# Communication.net
KiCad netlist of a schematic drawn in Altium Designer
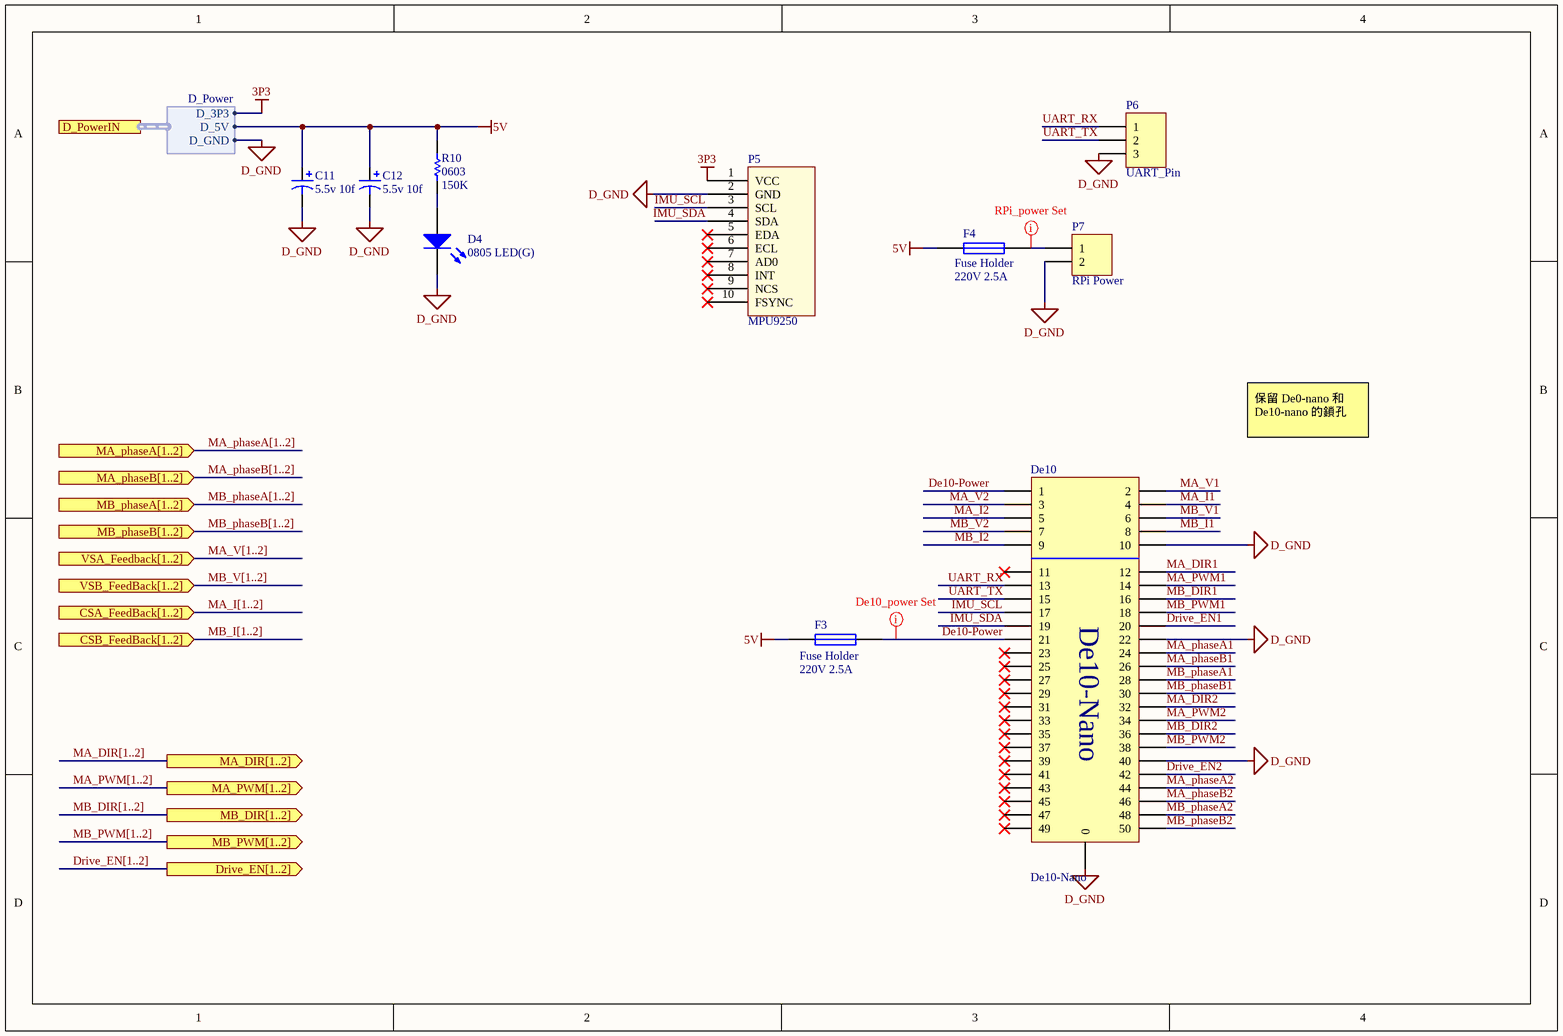
[diagram p0: Communication.SchDoc]

(export (version "E")
  (design (tool "Eeschema 10.0.6"))
  (components
    (comp (ref "C11")
      (value "5.5v 10f")
      (footprint "OWMR:SUPPYCAP-DIP_L33.0_W16.5")
      (description "Super Capacitor")
      (fields (field (name "PUBLISHER") "Altium Limited"))
      (libsource (lib "Miscellaneous Devices") (part "Cap Pol1"))
    )
    (comp (ref "C12")
      (value "5.5v 10f")
      (footprint "OWMR:SUPPYCAP-DIP_L33.0_W16.5")
      (description "Super Capacitor")
      (fields (field (name "PUBLISHER") "Altium Limited"))
      (libsource (lib "Miscellaneous Devices") (part "Cap Pol1"))
    )
    (comp (ref "D4")
      (value "0805 LED(G)")
      (footprint "OWMR:0805 SMD DIode")
      (description "Typical INFRARED GaAs LED")
      (fields (field (name "PUBLISHER") "Altium Limited"))
      (libsource (lib "Miscellaneous Devices") (part "LED0"))
    )
    (comp (ref "De10")
      (value "De10-Nano")
      (footprint "OWMR:De10-Nano")
      (libsource (lib "OWMR") (part "De10-Nano"))
    )
    (comp (ref "F3")
      (value "Fuse Holder")
      (footprint "OWMR:SMD Fuses Holder")
      (description "0451005.MRL")
      (fields (field (name "ALTIUM_VALUE") "220V 2.5A") (field (name "PUBLISHER") "Altium Limited"))
      (libsource (lib "Miscellaneous Devices") (part "Fuse 1"))
    )
    (comp (ref "F4")
      (value "Fuse Holder")
      (footprint "OWMR:SMD Fuses Holder")
      (description "0451005.MRL")
      (fields (field (name "ALTIUM_VALUE") "220V 2.5A") (field (name "PUBLISHER") "Altium Limited"))
      (libsource (lib "Miscellaneous Devices") (part "Fuse 1"))
    )
    (comp (ref "P5")
      (value "MPU9250")
      (footprint "MPU9250")
      (description "3 axis Gyro, Acceleration, Magmetic")
      (libsource (lib "OWMR") (part "IMU Pin"))
    )
    (comp (ref "P6")
      (value "UART_Pin")
      (footprint "OWMR:B3B-XH-A")
      (description "B3B-XH-A")
      (fields (field (name "PUBLISHER") "Altium Limited"))
      (libsource (lib "Miscellaneous Connectors") (part "Header 3"))
    )
    (comp (ref "P7")
      (value "RPi Power")
      (footprint "OWMR:B2B-XH-A")
      (description "B2B-XH-A")
      (fields (field (name "PUBLISHER") "Altium Limited"))
      (libsource (lib "Miscellaneous Connectors") (part "Header 2"))
    )
    (comp (ref "R10")
      (value "0603")
      (footprint "OWMR:0603 SMD Res")
      (description "Resistor")
      (fields (field (name "ALTIUM_VALUE") "150K") (field (name "PUBLISHER") "Altium Limited"))
      (libsource (lib "Miscellaneous Devices") (part "Res1"))
    )
  )
  (nets
    (net (code "2") (name "/De10-Power") (class "Default")
      (node (ref "De10") (pin "1") (pinfunction "1_1") (pintype "passive"))
      (node (ref "De10") (pin "21") (pinfunction "21_21") (pintype "passive"))
      (node (ref "F3") (pin "2") (pinfunction "2_2") (pintype "passive"))
    )
    (net (code "3") (name "/Drive_EN1") (class "Default")
      (node (ref "De10") (pin "20") (pinfunction "20_20") (pintype "passive"))
    )
    (net (code "4") (name "/Drive_EN2") (class "Default")
      (node (ref "De10") (pin "42") (pinfunction "42_42") (pintype "passive"))
    )
    (net (code "6") (name "/IMU_SCL") (class "Default")
      (node (ref "De10") (pin "17") (pinfunction "17_17") (pintype "passive"))
      (node (ref "P5") (pin "3") (pinfunction "SCL_3") (pintype "passive"))
    )
    (net (code "7") (name "/IMU_SDA") (class "Default")
      (node (ref "De10") (pin "19") (pinfunction "19_19") (pintype "passive"))
      (node (ref "P5") (pin "4") (pinfunction "SDA_4") (pintype "passive"))
    )
    (net (code "8") (name "/MA_DIR1") (class "Default")
      (node (ref "De10") (pin "12") (pinfunction "12_12") (pintype "passive"))
    )
    (net (code "9") (name "/MA_DIR2") (class "Default")
      (node (ref "De10") (pin "32") (pinfunction "32_32") (pintype "passive"))
    )
    (net (code "11") (name "/MA_I1") (class "Default")
      (node (ref "De10") (pin "4") (pinfunction "4_4") (pintype "passive"))
    )
    (net (code "12") (name "/MA_I2") (class "Default")
      (node (ref "De10") (pin "5") (pinfunction "5_5") (pintype "passive"))
    )
    (net (code "14") (name "/MA_PWM1") (class "Default")
      (node (ref "De10") (pin "14") (pinfunction "14_14") (pintype "passive"))
    )
    (net (code "15") (name "/MA_PWM2") (class "Default")
      (node (ref "De10") (pin "34") (pinfunction "34_34") (pintype "passive"))
    )
    (net (code "17") (name "/MA_V1") (class "Default")
      (node (ref "De10") (pin "2") (pinfunction "2_2") (pintype "passive"))
    )
    (net (code "18") (name "/MA_V2") (class "Default")
      (node (ref "De10") (pin "3") (pinfunction "3_3") (pintype "passive"))
    )
    (net (code "20") (name "/MA_phaseA1") (class "Default")
      (node (ref "De10") (pin "24") (pinfunction "24_24") (pintype "passive"))
    )
    (net (code "21") (name "/MA_phaseA2") (class "Default")
      (node (ref "De10") (pin "44") (pinfunction "44_44") (pintype "passive"))
    )
    (net (code "23") (name "/MA_phaseB1") (class "Default")
      (node (ref "De10") (pin "26") (pinfunction "26_26") (pintype "passive"))
    )
    (net (code "24") (name "/MA_phaseB2") (class "Default")
      (node (ref "De10") (pin "46") (pinfunction "46_46") (pintype "passive"))
    )
    (net (code "26") (name "/MB_DIR1") (class "Default")
      (node (ref "De10") (pin "16") (pinfunction "16_16") (pintype "passive"))
    )
    (net (code "27") (name "/MB_DIR2") (class "Default")
      (node (ref "De10") (pin "36") (pinfunction "36_36") (pintype "passive"))
    )
    (net (code "29") (name "/MB_I1") (class "Default")
      (node (ref "De10") (pin "8") (pinfunction "8_8") (pintype "passive"))
    )
    (net (code "30") (name "/MB_I2") (class "Default")
      (node (ref "De10") (pin "9") (pinfunction "9_9") (pintype "passive"))
    )
    (net (code "32") (name "/MB_PWM1") (class "Default")
      (node (ref "De10") (pin "18") (pinfunction "18_18") (pintype "passive"))
    )
    (net (code "33") (name "/MB_PWM2") (class "Default")
      (node (ref "De10") (pin "38") (pinfunction "38_38") (pintype "passive"))
    )
    (net (code "35") (name "/MB_V1") (class "Default")
      (node (ref "De10") (pin "6") (pinfunction "6_6") (pintype "passive"))
    )
    (net (code "36") (name "/MB_V2") (class "Default")
      (node (ref "De10") (pin "7") (pinfunction "7_7") (pintype "passive"))
    )
    (net (code "38") (name "/MB_phaseA1") (class "Default")
      (node (ref "De10") (pin "28") (pinfunction "28_28") (pintype "passive"))
    )
    (net (code "39") (name "/MB_phaseA2") (class "Default")
      (node (ref "De10") (pin "48") (pinfunction "48_48") (pintype "passive"))
    )
    (net (code "41") (name "/MB_phaseB1") (class "Default")
      (node (ref "De10") (pin "30") (pinfunction "30_30") (pintype "passive"))
    )
    (net (code "42") (name "/MB_phaseB2") (class "Default")
      (node (ref "De10") (pin "50") (pinfunction "50_50") (pintype "passive"))
    )
    (net (code "44") (name "/UART_RX") (class "Default")
      (node (ref "De10") (pin "13") (pinfunction "13_13") (pintype "passive"))
      (node (ref "P6") (pin "1") (pinfunction "1_1") (pintype "passive"))
    )
    (net (code "45") (name "/UART_TX") (class "Default")
      (node (ref "De10") (pin "15") (pinfunction "15_15") (pintype "passive"))
      (node (ref "P6") (pin "2") (pinfunction "2_2") (pintype "passive"))
    )
    (net (code "47") (name "3P3") (class "Default")
      (node (ref "P5") (pin "1") (pinfunction "VCC_1") (pintype "passive"))
    )
    (net (code "48") (name "5V") (class "Default")
      (node (ref "C11") (pin "1") (pinfunction "1_1") (pintype "passive"))
      (node (ref "C12") (pin "1") (pinfunction "1_1") (pintype "passive"))
      (node (ref "F3") (pin "1") (pinfunction "1_1") (pintype "passive"))
      (node (ref "F4") (pin "1") (pinfunction "1_1") (pintype "passive"))
      (node (ref "R10") (pin "2") (pinfunction "2_2") (pintype "passive"))
    )
    (net (code "49") (name "D_GND") (class "Default")
      (node (ref "C11") (pin "2") (pinfunction "2_2") (pintype "passive"))
      (node (ref "C12") (pin "2") (pinfunction "2_2") (pintype "passive"))
      (node (ref "D4") (pin "2") (pinfunction "K_2") (pintype "passive"))
      (node (ref "De10") (pin "0") (pinfunction "0_0") (pintype "passive"))
      (node (ref "De10") (pin "10") (pinfunction "10_10") (pintype "passive"))
      (node (ref "De10") (pin "22") (pinfunction "22_22") (pintype "passive"))
      (node (ref "De10") (pin "40") (pinfunction "40_40") (pintype "passive"))
      (node (ref "P5") (pin "2") (pinfunction "GND_2") (pintype "passive"))
      (node (ref "P6") (pin "3") (pinfunction "3_3") (pintype "passive"))
      (node (ref "P7") (pin "2") (pinfunction "2_2") (pintype "passive"))
    )
    (net (code "50") (name "Net-(D4-A)") (class "Default")
      (node (ref "D4") (pin "1") (pinfunction "A_1") (pintype "passive"))
      (node (ref "R10") (pin "1") (pinfunction "1_1") (pintype "passive"))
    )
    (net (code "51") (name "Net-(F4-Pad2)") (class "Default")
      (node (ref "F4") (pin "2") (pinfunction "2_2") (pintype "passive"))
      (node (ref "P7") (pin "1") (pinfunction "1_1") (pintype "passive"))
    )
    (net (code "52") (name "unconnected-(De10-Pad11)") (class "Default")
      (node (ref "De10") (pin "11") (pinfunction "11_11") (pintype "passive+no_connect"))
    )
    (net (code "53") (name "unconnected-(De10-Pad23)") (class "Default")
      (node (ref "De10") (pin "23") (pinfunction "23_23") (pintype "passive+no_connect"))
    )
    (net (code "54") (name "unconnected-(De10-Pad25)") (class "Default")
      (node (ref "De10") (pin "25") (pinfunction "25_25") (pintype "passive+no_connect"))
    )
    (net (code "55") (name "unconnected-(De10-Pad27)") (class "Default")
      (node (ref "De10") (pin "27") (pinfunction "27_27") (pintype "passive+no_connect"))
    )
    (net (code "56") (name "unconnected-(De10-Pad29)") (class "Default")
      (node (ref "De10") (pin "29") (pinfunction "29_29") (pintype "passive+no_connect"))
    )
    (net (code "57") (name "unconnected-(De10-Pad31)") (class "Default")
      (node (ref "De10") (pin "31") (pinfunction "31_31") (pintype "passive+no_connect"))
    )
    (net (code "58") (name "unconnected-(De10-Pad33)") (class "Default")
      (node (ref "De10") (pin "33") (pinfunction "33_33") (pintype "passive+no_connect"))
    )
    (net (code "59") (name "unconnected-(De10-Pad35)") (class "Default")
      (node (ref "De10") (pin "35") (pinfunction "35_35") (pintype "passive+no_connect"))
    )
    (net (code "60") (name "unconnected-(De10-Pad37)") (class "Default")
      (node (ref "De10") (pin "37") (pinfunction "37_37") (pintype "passive+no_connect"))
    )
    (net (code "61") (name "unconnected-(De10-Pad39)") (class "Default")
      (node (ref "De10") (pin "39") (pinfunction "39_39") (pintype "passive+no_connect"))
    )
    (net (code "62") (name "unconnected-(De10-Pad41)") (class "Default")
      (node (ref "De10") (pin "41") (pinfunction "41_41") (pintype "passive+no_connect"))
    )
    (net (code "63") (name "unconnected-(De10-Pad43)") (class "Default")
      (node (ref "De10") (pin "43") (pinfunction "43_43") (pintype "passive+no_connect"))
    )
    (net (code "64") (name "unconnected-(De10-Pad45)") (class "Default")
      (node (ref "De10") (pin "45") (pinfunction "45_45") (pintype "passive+no_connect"))
    )
    (net (code "65") (name "unconnected-(De10-Pad47)") (class "Default")
      (node (ref "De10") (pin "47") (pinfunction "47_47") (pintype "passive+no_connect"))
    )
    (net (code "66") (name "unconnected-(De10-Pad49)") (class "Default")
      (node (ref "De10") (pin "49") (pinfunction "49_49") (pintype "passive+no_connect"))
    )
    (net (code "67") (name "unconnected-(P5-AD0-Pad7)") (class "Default")
      (node (ref "P5") (pin "7") (pinfunction "AD0_7") (pintype "passive+no_connect"))
    )
    (net (code "68") (name "unconnected-(P5-ECL-Pad6)") (class "Default")
      (node (ref "P5") (pin "6") (pinfunction "ECL_6") (pintype "passive+no_connect"))
    )
    (net (code "69") (name "unconnected-(P5-EDA-Pad5)") (class "Default")
      (node (ref "P5") (pin "5") (pinfunction "EDA_5") (pintype "passive+no_connect"))
    )
    (net (code "70") (name "unconnected-(P5-FSYNC-Pad10)") (class "Default")
      (node (ref "P5") (pin "10") (pinfunction "FSYNC_10") (pintype "passive+no_connect"))
    )
    (net (code "71") (name "unconnected-(P5-INT-Pad8)") (class "Default")
      (node (ref "P5") (pin "8") (pinfunction "INT_8") (pintype "passive+no_connect"))
    )
    (net (code "72") (name "unconnected-(P5-NCS-Pad9)") (class "Default")
      (node (ref "P5") (pin "9") (pinfunction "NCS_9") (pintype "passive+no_connect"))
    )
  )
)
